# profile.net
KiCad netlist of a schematic drawn in EAGLE
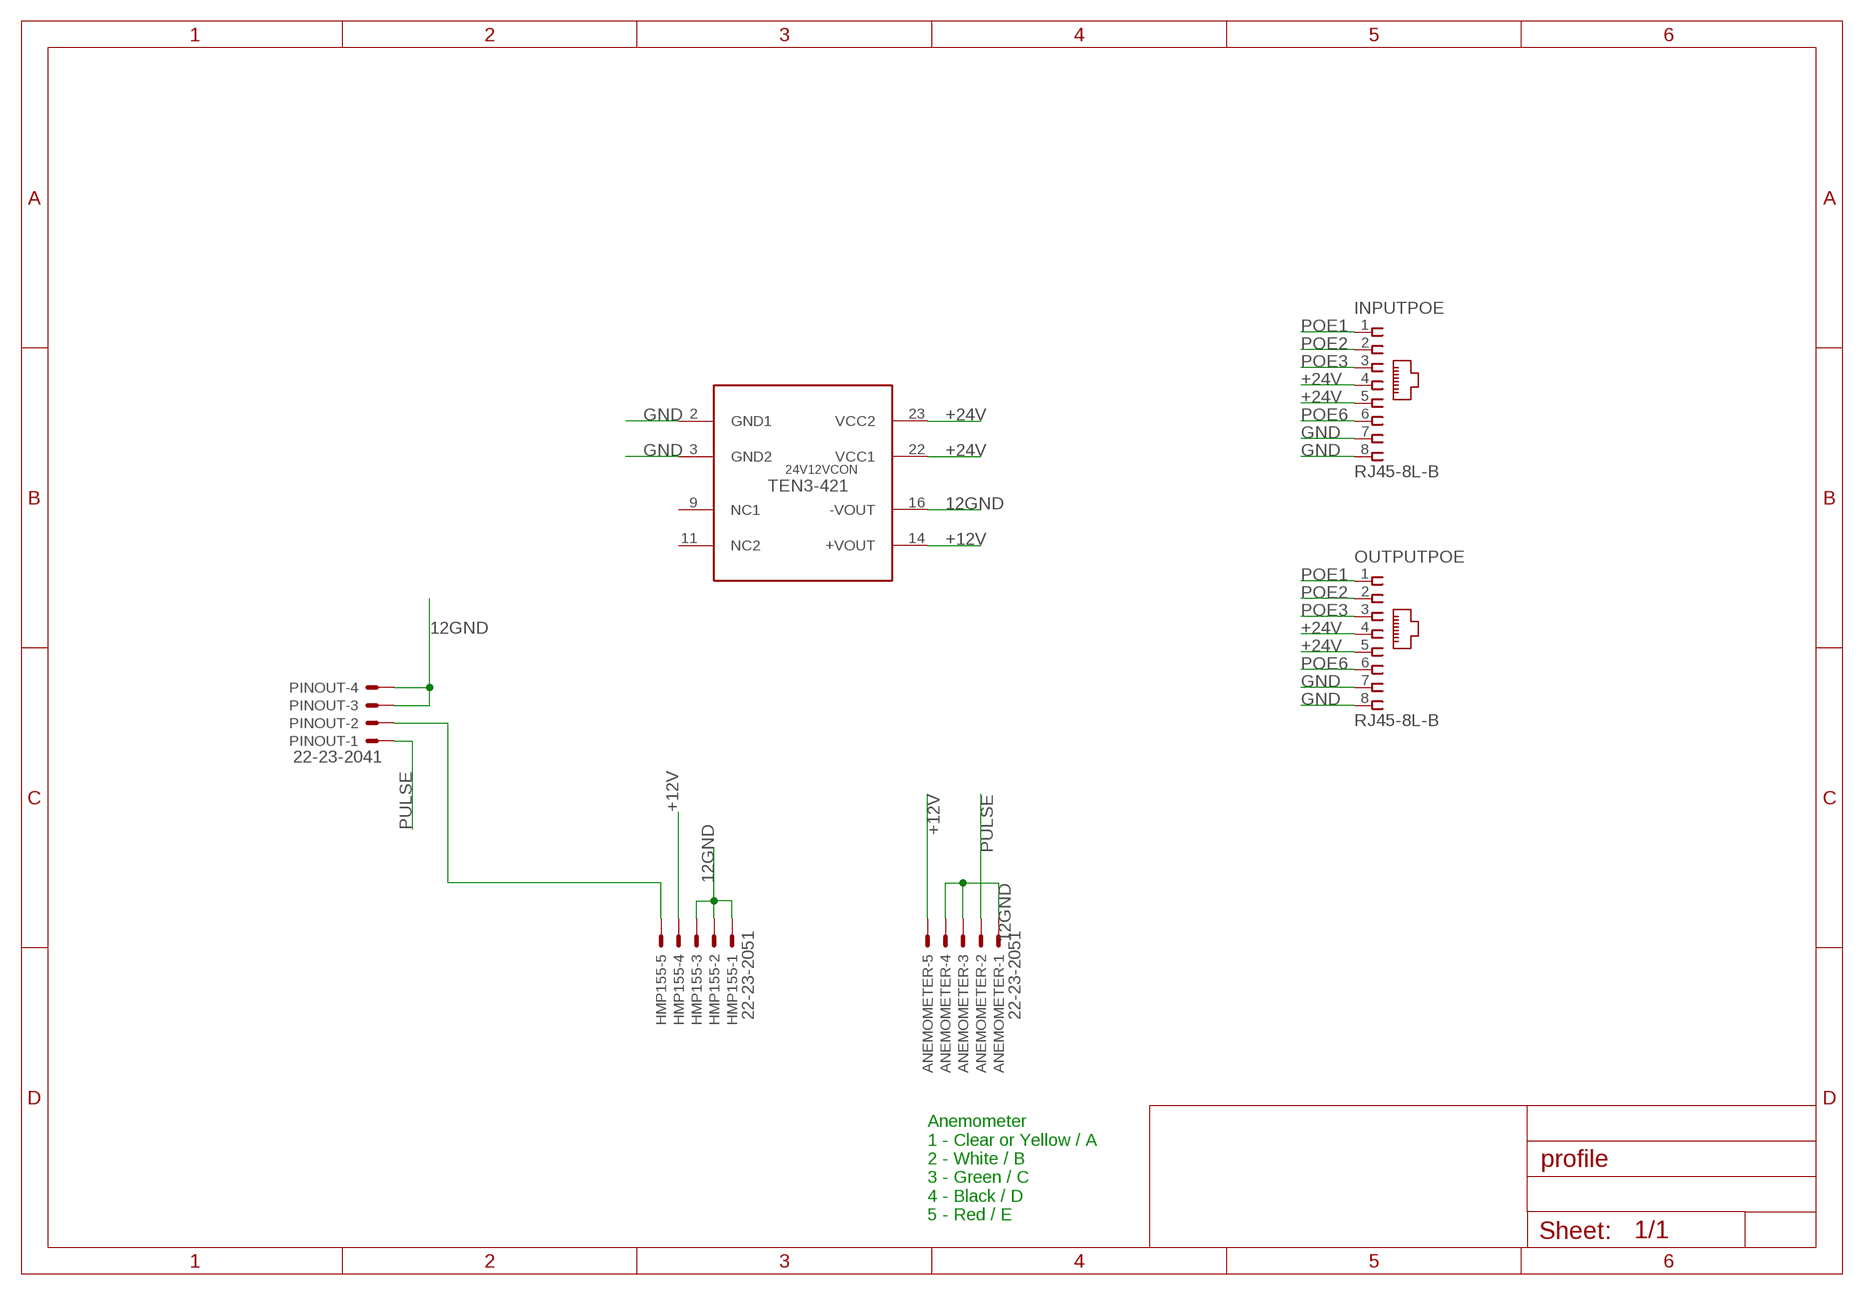
[diagram p0: schematic, sheet 1]

(export (version "E")
  (design (tool "Eeschema 10.0.6"))
  (components
    (comp (ref "24V12VCON")
      (value "TEN3-421")
      (footprint "eagle-import:SOCKET-24-6")
      (libsource (lib "eagle-import") (part "TEN3-421"))
    )
    (comp (ref "ANEMOMETER")
      (value "22-23-2051")
      (footprint "eagle-import:22-23-2051")
      (fields (field (name "MF") "MOLEX"))
      (libsource (lib "eagle-import") (part "22-23-2051"))
    )
    (comp (ref "HMP155")
      (value "22-23-2051")
      (footprint "eagle-import:22-23-2051")
      (fields (field (name "MF") "MOLEX"))
      (libsource (lib "eagle-import") (part "22-23-2051"))
    )
    (comp (ref "INPUTPOE")
      (value "RJ45-8L-B")
      (footprint "eagle-import:RJ45-NO-SHIELD")
      (fields (field (name "MF") "TYCO ELECTRONICS"))
      (libsource (lib "eagle-import") (part "RJ45-8L-B"))
    )
    (comp (ref "OUTPUTPOE")
      (value "RJ45-8L-B")
      (footprint "eagle-import:RJ45-NO-SHIELD")
      (fields (field (name "MF") "TYCO ELECTRONICS"))
      (libsource (lib "eagle-import") (part "RJ45-8L-B"))
    )
    (comp (ref "PINOUT")
      (value "22-23-2041")
      (footprint "eagle-import:22-23-2041")
      (fields (field (name "MF") "MOLEX"))
      (libsource (lib "eagle-import") (part "22-23-2041"))
    )
  )
  (nets
    (net (code "1") (name "/+12V") (class "Default")
      (node (ref "24V12VCON") (pin "14") (pinfunction "+VOUT_14") (pintype "bidirectional"))
      (node (ref "ANEMOMETER") (pin "5") (pinfunction "S_5") (pintype "passive"))
      (node (ref "HMP155") (pin "4") (pinfunction "S_4") (pintype "passive"))
    )
    (net (code "2") (name "/+24V") (class "Default")
      (node (ref "24V12VCON") (pin "22") (pinfunction "VCC1_22") (pintype "bidirectional"))
      (node (ref "24V12VCON") (pin "23") (pinfunction "VCC2_23") (pintype "bidirectional"))
      (node (ref "INPUTPOE") (pin "4") (pinfunction "4_4") (pintype "passive"))
      (node (ref "INPUTPOE") (pin "5") (pinfunction "5_5") (pintype "passive"))
      (node (ref "OUTPUTPOE") (pin "4") (pinfunction "4_4") (pintype "passive"))
      (node (ref "OUTPUTPOE") (pin "5") (pinfunction "5_5") (pintype "passive"))
    )
    (net (code "3") (name "/12GND") (class "Default")
      (node (ref "24V12VCON") (pin "16") (pinfunction "-VOUT_16") (pintype "bidirectional"))
      (node (ref "ANEMOMETER") (pin "1") (pinfunction "S_1") (pintype "passive"))
      (node (ref "ANEMOMETER") (pin "3") (pinfunction "S_3") (pintype "passive"))
      (node (ref "ANEMOMETER") (pin "4") (pinfunction "S_4") (pintype "passive"))
      (node (ref "HMP155") (pin "1") (pinfunction "S_1") (pintype "passive"))
      (node (ref "HMP155") (pin "2") (pinfunction "S_2") (pintype "passive"))
      (node (ref "HMP155") (pin "3") (pinfunction "S_3") (pintype "passive"))
      (node (ref "PINOUT") (pin "3") (pinfunction "S_3") (pintype "passive"))
      (node (ref "PINOUT") (pin "4") (pinfunction "S_4") (pintype "passive"))
    )
    (net (code "4") (name "/GND") (class "Default")
      (node (ref "24V12VCON") (pin "2") (pinfunction "GND1_2") (pintype "bidirectional"))
      (node (ref "24V12VCON") (pin "3") (pinfunction "GND2_3") (pintype "bidirectional"))
      (node (ref "INPUTPOE") (pin "7") (pinfunction "7_7") (pintype "passive"))
      (node (ref "INPUTPOE") (pin "8") (pinfunction "8_8") (pintype "passive"))
      (node (ref "OUTPUTPOE") (pin "7") (pinfunction "7_7") (pintype "passive"))
      (node (ref "OUTPUTPOE") (pin "8") (pinfunction "8_8") (pintype "passive"))
    )
    (net (code "5") (name "/POE1") (class "Default")
      (node (ref "INPUTPOE") (pin "1") (pinfunction "1_1") (pintype "passive"))
      (node (ref "OUTPUTPOE") (pin "1") (pinfunction "1_1") (pintype "passive"))
    )
    (net (code "6") (name "/POE2") (class "Default")
      (node (ref "INPUTPOE") (pin "2") (pinfunction "2_2") (pintype "passive"))
      (node (ref "OUTPUTPOE") (pin "2") (pinfunction "2_2") (pintype "passive"))
    )
    (net (code "7") (name "/POE3") (class "Default")
      (node (ref "INPUTPOE") (pin "3") (pinfunction "3_3") (pintype "passive"))
      (node (ref "OUTPUTPOE") (pin "3") (pinfunction "3_3") (pintype "passive"))
    )
    (net (code "8") (name "/POE6") (class "Default")
      (node (ref "INPUTPOE") (pin "6") (pinfunction "6_6") (pintype "passive"))
      (node (ref "OUTPUTPOE") (pin "6") (pinfunction "6_6") (pintype "passive"))
    )
    (net (code "9") (name "/PULSE") (class "Default")
      (node (ref "ANEMOMETER") (pin "2") (pinfunction "S_2") (pintype "passive"))
      (node (ref "PINOUT") (pin "1") (pinfunction "S_1") (pintype "passive"))
    )
    (net (code "10") (name "Net-(HMP155E-S)") (class "Default")
      (node (ref "HMP155") (pin "5") (pinfunction "S_5") (pintype "passive"))
      (node (ref "PINOUT") (pin "2") (pinfunction "S_2") (pintype "passive"))
    )
    (net (code "11") (name "unconnected-(24V12VCON-NC1-Pad9)") (class "Default")
      (node (ref "24V12VCON") (pin "9") (pinfunction "NC1_9") (pintype "bidirectional"))
    )
    (net (code "12") (name "unconnected-(24V12VCON-NC2-Pad11)") (class "Default")
      (node (ref "24V12VCON") (pin "11") (pinfunction "NC2_11") (pintype "bidirectional"))
    )
  )
)
